# LTC_Connector_Interface.net
KiCad netlist of a schematic drawn in EAGLE
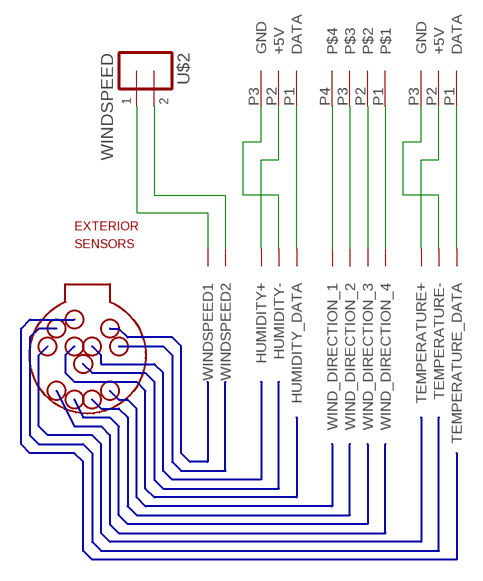
[diagram p0: schematic, sheet 1]

(export (version "E")
  (design (tool "Eeschema 10.0.6"))
  (components
    (comp (ref "HUMIDITY")
      (value "MOLEX-3")
      (footprint "eagle-import:MOLEX-3")
      (libsource (lib "eagle-import") (part "MOLEX-3"))
    )
    (comp (ref "TEMP")
      (value "MOLEX-3")
      (footprint "eagle-import:MOLEX-3")
      (libsource (lib "eagle-import") (part "MOLEX-3"))
    )
    (comp (ref "U$1")
      (value "LAYOUT-LEMO-12PIN")
      (footprint "eagle-import:LEMO-12")
      (libsource (lib "eagle-import") (part "LAYOUT-LEMO-12PIN"))
    )
    (comp (ref "U$2")
      (value "WINDSPEED")
      (footprint "eagle-import:SCREW-TERM-5MM")
      (libsource (lib "eagle-import") (part "SCREW-TERMINAL-5MM"))
    )
    (comp (ref "WINDDIRECTION")
      (value "MOLEX-4")
      (footprint "eagle-import:MOLEX-4")
      (libsource (lib "eagle-import") (part "MOLEX-4"))
    )
  )
  (nets
    (net (code "1") (name "Net-(HUMIDITY-+5V)") (class "Default")
      (node (ref "HUMIDITY") (pin "P2") (pinfunction "+5V_P2") (pintype "bidirectional"))
      (node (ref "U$1") (pin "P12") (pinfunction "HUMIDITY+_P12") (pintype "bidirectional"))
    )
    (net (code "2") (name "Net-(HUMIDITY-DATA)") (class "Default")
      (node (ref "HUMIDITY") (pin "P1") (pinfunction "DATA_P1") (pintype "bidirectional"))
      (node (ref "U$1") (pin "P2") (pinfunction "HUMIDITY_DATA_P2") (pintype "bidirectional"))
    )
    (net (code "3") (name "Net-(HUMIDITY-GND)") (class "Default")
      (node (ref "HUMIDITY") (pin "P3") (pinfunction "GND_P3") (pintype "bidirectional"))
      (node (ref "U$1") (pin "P9") (pinfunction "HUMIDITY-_P9") (pintype "bidirectional"))
    )
    (net (code "4") (name "Net-(TEMP-+5V)") (class "Default")
      (node (ref "TEMP") (pin "P2") (pinfunction "+5V_P2") (pintype "bidirectional"))
      (node (ref "U$1") (pin "P7") (pinfunction "TEMPERATURE+_P7") (pintype "bidirectional"))
    )
    (net (code "5") (name "Net-(TEMP-DATA)") (class "Default")
      (node (ref "TEMP") (pin "P1") (pinfunction "DATA_P1") (pintype "bidirectional"))
      (node (ref "U$1") (pin "P1") (pinfunction "TEMPERATURE_DATA_P1") (pintype "bidirectional"))
    )
    (net (code "6") (name "Net-(TEMP-GND)") (class "Default")
      (node (ref "TEMP") (pin "P3") (pinfunction "GND_P3") (pintype "bidirectional"))
      (node (ref "U$1") (pin "P8") (pinfunction "TEMPERATURE-_P8") (pintype "bidirectional"))
    )
    (net (code "7") (name "Net-(U$1-WINDSPEED1)") (class "Default")
      (node (ref "U$1") (pin "P6") (pinfunction "WINDSPEED1_P6") (pintype "bidirectional"))
      (node (ref "U$2") (pin "1") (pinfunction "1_1") (pintype "passive"))
    )
    (net (code "8") (name "Net-(U$1-WINDSPEED2)") (class "Default")
      (node (ref "U$1") (pin "P5") (pinfunction "WINDSPEED2_P5") (pintype "bidirectional"))
      (node (ref "U$2") (pin "2") (pinfunction "2_2") (pintype "passive"))
    )
    (net (code "9") (name "Net-(U$1-WIND_DIRECTION_1)") (class "Default")
      (node (ref "U$1") (pin "P11") (pinfunction "WIND_DIRECTION_1_P11") (pintype "bidirectional"))
      (node (ref "WINDDIRECTION") (pin "P4") (pinfunction "P$4_P4") (pintype "bidirectional"))
    )
    (net (code "10") (name "Net-(U$1-WIND_DIRECTION_2)") (class "Default")
      (node (ref "U$1") (pin "P10") (pinfunction "WIND_DIRECTION_2_P10") (pintype "bidirectional"))
      (node (ref "WINDDIRECTION") (pin "P3") (pinfunction "P$3_P3") (pintype "bidirectional"))
    )
    (net (code "11") (name "Net-(U$1-WIND_DIRECTION_3)") (class "Default")
      (node (ref "U$1") (pin "P3") (pinfunction "WIND_DIRECTION_3_P3") (pintype "bidirectional"))
      (node (ref "WINDDIRECTION") (pin "P2") (pinfunction "P$2_P2") (pintype "bidirectional"))
    )
    (net (code "12") (name "Net-(U$1-WIND_DIRECTION_4)") (class "Default")
      (node (ref "U$1") (pin "P4") (pinfunction "WIND_DIRECTION_4_P4") (pintype "bidirectional"))
      (node (ref "WINDDIRECTION") (pin "P1") (pinfunction "P$1_P1") (pintype "bidirectional"))
    )
  )
)
